# Sheet1.net
KiCad netlist of a schematic drawn in Altium Designer
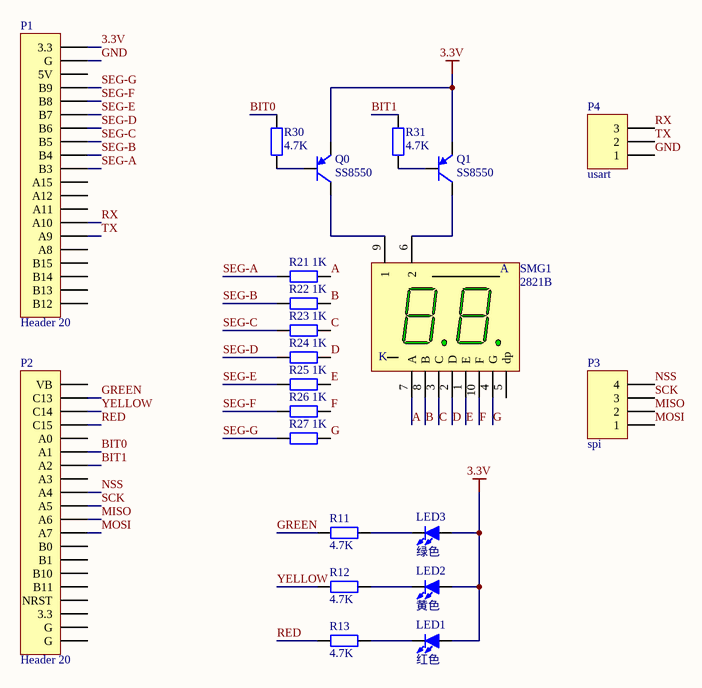
[diagram p0: Sheet1.SchDoc]

(export (version "E")
  (design (tool "Eeschema 10.0.6"))
  (components
    (comp (ref "LED1")
      (value "红色")
      (footprint "LED 0805G")
      (description "贴片LED")
      (fields (field (name "版权归属") "源创客"))
      (libsource (lib "LED") (part "LED-SMD"))
    )
    (comp (ref "LED2")
      (value "黄色")
      (footprint "LED 0805G")
      (description "贴片LED")
      (fields (field (name "版权归属") "源创客"))
      (libsource (lib "LED") (part "LED-SMD"))
    )
    (comp (ref "LED3")
      (value "绿色")
      (footprint "LED 0805G")
      (description "贴片LED")
      (fields (field (name "版权归属") "源创客"))
      (libsource (lib "LED") (part "LED-SMD"))
    )
    (comp (ref "P1")
      (value "Header 20")
      (footprint "HDR1X20")
      (description "Header, 20-Pin")
      (fields (field (name "PUBLISHER") "Altium Limited"))
      (libsource (lib "Miscellaneous Connectors") (part "Header 20"))
    )
    (comp (ref "P2")
      (value "Header 20")
      (footprint "HDR1X20")
      (description "Header, 20-Pin")
      (fields (field (name "PUBLISHER") "Altium Limited"))
      (libsource (lib "Miscellaneous Connectors") (part "Header 20"))
    )
    (comp (ref "P3")
      (value "spi")
      (footprint "HDR1X4")
      (description "Header, 4-Pin")
      (fields (field (name "PUBLISHER") "Altium Limited"))
      (libsource (lib "Miscellaneous Connectors") (part "Header 4"))
    )
    (comp (ref "P4")
      (value "usart")
      (footprint "HDR1X3")
      (description "Header, 3-Pin")
      (fields (field (name "PUBLISHER") "Altium Limited"))
      (libsource (lib "Miscellaneous Connectors") (part "Header 3"))
    )
    (comp (ref "Q0")
      (value "SS8550")
      (footprint "SOT23-3N")
      (description "高频放大-PNP型")
      (fields (field (name "版权归属") "源创客"))
      (libsource (lib "三极管") (part "8550-SMD"))
    )
    (comp (ref "Q1")
      (value "SS8550")
      (footprint "SOT23-3N")
      (description "高频放大-PNP型")
      (fields (field (name "版权归属") "源创客"))
      (libsource (lib "三极管") (part "8550-SMD"))
    )
    (comp (ref "R11")
      (value "4.7K")
      (footprint "R 0805")
      (description "贴片电阻")
      (fields (field (name "版权归属") "源创客"))
      (libsource (lib "电阻-电容-电感") (part "R"))
    )
    (comp (ref "R12")
      (value "4.7K")
      (footprint "R 0805")
      (description "贴片电阻")
      (fields (field (name "版权归属") "源创客"))
      (libsource (lib "电阻-电容-电感") (part "R"))
    )
    (comp (ref "R13")
      (value "4.7K")
      (footprint "R 0805")
      (description "贴片电阻")
      (fields (field (name "版权归属") "源创客"))
      (libsource (lib "电阻-电容-电感") (part "R"))
    )
    (comp (ref "R21")
      (value "1K")
      (footprint "R 0805")
      (description "贴片电阻")
      (fields (field (name "版权归属") "源创客"))
      (libsource (lib "电阻-电容-电感") (part "R"))
    )
    (comp (ref "R22")
      (value "1K")
      (footprint "R 0805")
      (description "贴片电阻")
      (fields (field (name "版权归属") "源创客"))
      (libsource (lib "电阻-电容-电感") (part "R"))
    )
    (comp (ref "R23")
      (value "1K")
      (footprint "R 0805")
      (description "贴片电阻")
      (fields (field (name "版权归属") "源创客"))
      (libsource (lib "电阻-电容-电感") (part "R"))
    )
    (comp (ref "R24")
      (value "1K")
      (footprint "R 0805")
      (description "贴片电阻")
      (fields (field (name "版权归属") "源创客"))
      (libsource (lib "电阻-电容-电感") (part "R"))
    )
    (comp (ref "R25")
      (value "1K")
      (footprint "R 0805")
      (description "贴片电阻")
      (fields (field (name "版权归属") "源创客"))
      (libsource (lib "电阻-电容-电感") (part "R"))
    )
    (comp (ref "R26")
      (value "1K")
      (footprint "R 0805")
      (description "贴片电阻")
      (fields (field (name "版权归属") "源创客"))
      (libsource (lib "电阻-电容-电感") (part "R"))
    )
    (comp (ref "R27")
      (value "1K")
      (footprint "R 0805")
      (description "贴片电阻")
      (fields (field (name "版权归属") "源创客"))
      (libsource (lib "电阻-电容-电感") (part "R"))
    )
    (comp (ref "R30")
      (value "4.7K")
      (footprint "R 0805")
      (description "贴片电阻")
      (fields (field (name "版权归属") "源创客"))
      (libsource (lib "电阻-电容-电感") (part "R"))
    )
    (comp (ref "R31")
      (value "4.7K")
      (footprint "R 0805")
      (description "贴片电阻")
      (fields (field (name "版权归属") "源创客"))
      (libsource (lib "电阻-电容-电感") (part "R"))
    )
    (comp (ref "SMG1")
      (value "2821B")
      (footprint "SMG 0.28-2P")
      (description "0.28寸2位共阳数码管")
      (fields (field (name "版权归属") "源创客"))
      (libsource (lib "显示器件") (part "2821B"))
    )
  )
  (nets
    (net (code "1") (name "/A") (class "Default")
      (node (ref "R21") (pin "2") (pinfunction "2_2") (pintype "passive"))
      (node (ref "SMG1") (pin "7") (pinfunction "A_7") (pintype "passive"))
    )
    (net (code "2") (name "/B") (class "Default")
      (node (ref "R22") (pin "2") (pinfunction "2_2") (pintype "passive"))
      (node (ref "SMG1") (pin "8") (pinfunction "B_8") (pintype "passive"))
    )
    (net (code "3") (name "/BIT0") (class "Default")
      (node (ref "P2") (pin "15") (pinfunction "B7_15") (pintype "passive"))
      (node (ref "R30") (pin "2") (pinfunction "2_2") (pintype "passive"))
    )
    (net (code "4") (name "/BIT1") (class "Default")
      (node (ref "P2") (pin "14") (pinfunction "B6_14") (pintype "passive"))
      (node (ref "R31") (pin "2") (pinfunction "2_2") (pintype "passive"))
    )
    (net (code "5") (name "/C") (class "Default")
      (node (ref "R23") (pin "2") (pinfunction "2_2") (pintype "passive"))
      (node (ref "SMG1") (pin "3") (pinfunction "C_3") (pintype "passive"))
    )
    (net (code "6") (name "/D") (class "Default")
      (node (ref "R24") (pin "2") (pinfunction "2_2") (pintype "passive"))
      (node (ref "SMG1") (pin "2") (pinfunction "D_2") (pintype "passive"))
    )
    (net (code "7") (name "/E") (class "Default")
      (node (ref "R25") (pin "2") (pinfunction "2_2") (pintype "passive"))
      (node (ref "SMG1") (pin "1") (pinfunction "E_1") (pintype "passive"))
    )
    (net (code "8") (name "/F") (class "Default")
      (node (ref "R26") (pin "2") (pinfunction "2_2") (pintype "passive"))
      (node (ref "SMG1") (pin "10") (pinfunction "F_10") (pintype "passive"))
    )
    (net (code "9") (name "/G") (class "Default")
      (node (ref "R27") (pin "2") (pinfunction "2_2") (pintype "passive"))
      (node (ref "SMG1") (pin "4") (pinfunction "G_4") (pintype "passive"))
    )
    (net (code "10") (name "/GND") (class "Default")
      (node (ref "P1") (pin "19") (pinfunction "G_19") (pintype "passive"))
      (node (ref "P4") (pin "1") (pinfunction "1_1") (pintype "passive"))
    )
    (net (code "11") (name "/GREEN") (class "Default")
      (node (ref "P2") (pin "19") (pinfunction "G_19") (pintype "passive"))
      (node (ref "R11") (pin "1") (pinfunction "1_1") (pintype "passive"))
    )
    (net (code "12") (name "/MISO") (class "Default")
      (node (ref "P2") (pin "10") (pinfunction "A15_10") (pintype "passive"))
      (node (ref "P3") (pin "2") (pinfunction "2_2") (pintype "passive"))
    )
    (net (code "13") (name "/MOSI") (class "Default")
      (node (ref "P2") (pin "9") (pinfunction "A12_9") (pintype "passive"))
      (node (ref "P3") (pin "1") (pinfunction "1_1") (pintype "passive"))
    )
    (net (code "14") (name "/NSS") (class "Default")
      (node (ref "P2") (pin "12") (pinfunction "B4_12") (pintype "passive"))
      (node (ref "P3") (pin "4") (pinfunction "4_4") (pintype "passive"))
    )
    (net (code "15") (name "/RED") (class "Default")
      (node (ref "P2") (pin "17") (pinfunction "B9_17") (pintype "passive"))
      (node (ref "R13") (pin "1") (pinfunction "1_1") (pintype "passive"))
    )
    (net (code "16") (name "/RX") (class "Default")
      (node (ref "P1") (pin "7") (pinfunction "A10_7") (pintype "passive"))
      (node (ref "P4") (pin "3") (pinfunction "3_3") (pintype "passive"))
    )
    (net (code "17") (name "/SCK") (class "Default")
      (node (ref "P2") (pin "11") (pinfunction "B3_11") (pintype "passive"))
      (node (ref "P3") (pin "3") (pinfunction "3_3") (pintype "passive"))
    )
    (net (code "18") (name "/SEG-A") (class "Default")
      (node (ref "P1") (pin "11") (pinfunction "B3_11") (pintype "passive"))
      (node (ref "R21") (pin "1") (pinfunction "1_1") (pintype "passive"))
    )
    (net (code "19") (name "/SEG-B") (class "Default")
      (node (ref "P1") (pin "12") (pinfunction "B4_12") (pintype "passive"))
      (node (ref "R22") (pin "1") (pinfunction "1_1") (pintype "passive"))
    )
    (net (code "20") (name "/SEG-C") (class "Default")
      (node (ref "P1") (pin "13") (pinfunction "B5_13") (pintype "passive"))
      (node (ref "R23") (pin "1") (pinfunction "1_1") (pintype "passive"))
    )
    (net (code "21") (name "/SEG-D") (class "Default")
      (node (ref "P1") (pin "14") (pinfunction "B6_14") (pintype "passive"))
      (node (ref "R24") (pin "1") (pinfunction "1_1") (pintype "passive"))
    )
    (net (code "22") (name "/SEG-E") (class "Default")
      (node (ref "P1") (pin "15") (pinfunction "B7_15") (pintype "passive"))
      (node (ref "R25") (pin "1") (pinfunction "1_1") (pintype "passive"))
    )
    (net (code "23") (name "/SEG-F") (class "Default")
      (node (ref "P1") (pin "16") (pinfunction "B8_16") (pintype "passive"))
      (node (ref "R26") (pin "1") (pinfunction "1_1") (pintype "passive"))
    )
    (net (code "24") (name "/SEG-G") (class "Default")
      (node (ref "P1") (pin "17") (pinfunction "B9_17") (pintype "passive"))
      (node (ref "R27") (pin "1") (pinfunction "1_1") (pintype "passive"))
    )
    (net (code "25") (name "/TX") (class "Default")
      (node (ref "P1") (pin "6") (pinfunction "A9_6") (pintype "passive"))
      (node (ref "P4") (pin "2") (pinfunction "2_2") (pintype "passive"))
    )
    (net (code "26") (name "/YELLOW") (class "Default")
      (node (ref "P2") (pin "18") (pinfunction "5V_18") (pintype "passive"))
      (node (ref "R12") (pin "1") (pinfunction "1_1") (pintype "passive"))
    )
    (net (code "27") (name "3.3V") (class "Default")
      (node (ref "LED1") (pin "1") (pinfunction "A_1") (pintype "passive"))
      (node (ref "LED2") (pin "1") (pinfunction "A_1") (pintype "passive"))
      (node (ref "LED3") (pin "1") (pinfunction "A_1") (pintype "passive"))
      (node (ref "P1") (pin "20") (pinfunction "3.3_20") (pintype "passive"))
      (node (ref "Q0") (pin "2") (pinfunction "E_2") (pintype "passive"))
      (node (ref "Q1") (pin "2") (pinfunction "E_2") (pintype "passive"))
    )
    (net (code "28") (name "Net-(LED1-K)") (class "Default")
      (node (ref "LED1") (pin "2") (pinfunction "K_2") (pintype "passive"))
      (node (ref "R13") (pin "2") (pinfunction "2_2") (pintype "passive"))
    )
    (net (code "29") (name "Net-(LED2-K)") (class "Default")
      (node (ref "LED2") (pin "2") (pinfunction "K_2") (pintype "passive"))
      (node (ref "R12") (pin "2") (pinfunction "2_2") (pintype "passive"))
    )
    (net (code "30") (name "Net-(LED3-K)") (class "Default")
      (node (ref "LED3") (pin "2") (pinfunction "K_2") (pintype "passive"))
      (node (ref "R11") (pin "2") (pinfunction "2_2") (pintype "passive"))
    )
    (net (code "31") (name "Net-(Q0-B)") (class "Default")
      (node (ref "Q0") (pin "1") (pinfunction "B_1") (pintype "passive"))
      (node (ref "R30") (pin "1") (pinfunction "1_1") (pintype "passive"))
    )
    (net (code "32") (name "Net-(Q0-C)") (class "Default")
      (node (ref "Q0") (pin "3") (pinfunction "C_3") (pintype "passive"))
      (node (ref "SMG1") (pin "9") (pinfunction "1_9") (pintype "passive"))
    )
    (net (code "33") (name "Net-(Q1-B)") (class "Default")
      (node (ref "Q1") (pin "1") (pinfunction "B_1") (pintype "passive"))
      (node (ref "R31") (pin "1") (pinfunction "1_1") (pintype "passive"))
    )
    (net (code "34") (name "Net-(Q1-C)") (class "Default")
      (node (ref "Q1") (pin "3") (pinfunction "C_3") (pintype "passive"))
      (node (ref "SMG1") (pin "6") (pinfunction "2_6") (pintype "passive"))
    )
    (net (code "35") (name "unconnected-(P1-5V-Pad18)") (class "Default")
      (node (ref "P1") (pin "18") (pinfunction "5V_18") (pintype "passive"))
    )
    (net (code "36") (name "unconnected-(P1-A8-Pad5)") (class "Default")
      (node (ref "P1") (pin "5") (pinfunction "A8_5") (pintype "passive"))
    )
    (net (code "37") (name "unconnected-(P1-A11-Pad8)") (class "Default")
      (node (ref "P1") (pin "8") (pinfunction "A11_8") (pintype "passive"))
    )
    (net (code "38") (name "unconnected-(P1-A12-Pad9)") (class "Default")
      (node (ref "P1") (pin "9") (pinfunction "A12_9") (pintype "passive"))
    )
    (net (code "39") (name "unconnected-(P1-A15-Pad10)") (class "Default")
      (node (ref "P1") (pin "10") (pinfunction "A15_10") (pintype "passive"))
    )
    (net (code "40") (name "unconnected-(P1-B12-Pad1)") (class "Default")
      (node (ref "P1") (pin "1") (pinfunction "B12_1") (pintype "passive"))
    )
    (net (code "41") (name "unconnected-(P1-B13-Pad2)") (class "Default")
      (node (ref "P1") (pin "2") (pinfunction "B13_2") (pintype "passive"))
    )
    (net (code "42") (name "unconnected-(P1-B14-Pad3)") (class "Default")
      (node (ref "P1") (pin "3") (pinfunction "B14_3") (pintype "passive"))
    )
    (net (code "43") (name "unconnected-(P1-B15-Pad4)") (class "Default")
      (node (ref "P1") (pin "4") (pinfunction "B15_4") (pintype "passive"))
    )
    (net (code "44") (name "unconnected-(P2-3.3-Pad20)") (class "Default")
      (node (ref "P2") (pin "20") (pinfunction "3.3_20") (pintype "passive"))
    )
    (net (code "45") (name "unconnected-(P2-A8-Pad5)") (class "Default")
      (node (ref "P2") (pin "5") (pinfunction "A8_5") (pintype "passive"))
    )
    (net (code "46") (name "unconnected-(P2-A9-Pad6)") (class "Default")
      (node (ref "P2") (pin "6") (pinfunction "A9_6") (pintype "passive"))
    )
    (net (code "47") (name "unconnected-(P2-A10-Pad7)") (class "Default")
      (node (ref "P2") (pin "7") (pinfunction "A10_7") (pintype "passive"))
    )
    (net (code "48") (name "unconnected-(P2-A11-Pad8)") (class "Default")
      (node (ref "P2") (pin "8") (pinfunction "A11_8") (pintype "passive"))
    )
    (net (code "49") (name "unconnected-(P2-B5-Pad13)") (class "Default")
      (node (ref "P2") (pin "13") (pinfunction "B5_13") (pintype "passive"))
    )
    (net (code "50") (name "unconnected-(P2-B8-Pad16)") (class "Default")
      (node (ref "P2") (pin "16") (pinfunction "B8_16") (pintype "passive"))
    )
    (net (code "51") (name "unconnected-(P2-B12-Pad1)") (class "Default")
      (node (ref "P2") (pin "1") (pinfunction "B12_1") (pintype "passive"))
    )
    (net (code "52") (name "unconnected-(P2-B13-Pad2)") (class "Default")
      (node (ref "P2") (pin "2") (pinfunction "B13_2") (pintype "passive"))
    )
    (net (code "53") (name "unconnected-(P2-B14-Pad3)") (class "Default")
      (node (ref "P2") (pin "3") (pinfunction "B14_3") (pintype "passive"))
    )
    (net (code "54") (name "unconnected-(P2-B15-Pad4)") (class "Default")
      (node (ref "P2") (pin "4") (pinfunction "B15_4") (pintype "passive"))
    )
    (net (code "55") (name "unconnected-(SMG1-dp-Pad5)") (class "Default")
      (node (ref "SMG1") (pin "5") (pinfunction "dp_5") (pintype "passive"))
    )
  )
)
